# Voltmeter_PCB_RTC_f.net
KiCad netlist of a schematic drawn in EAGLE
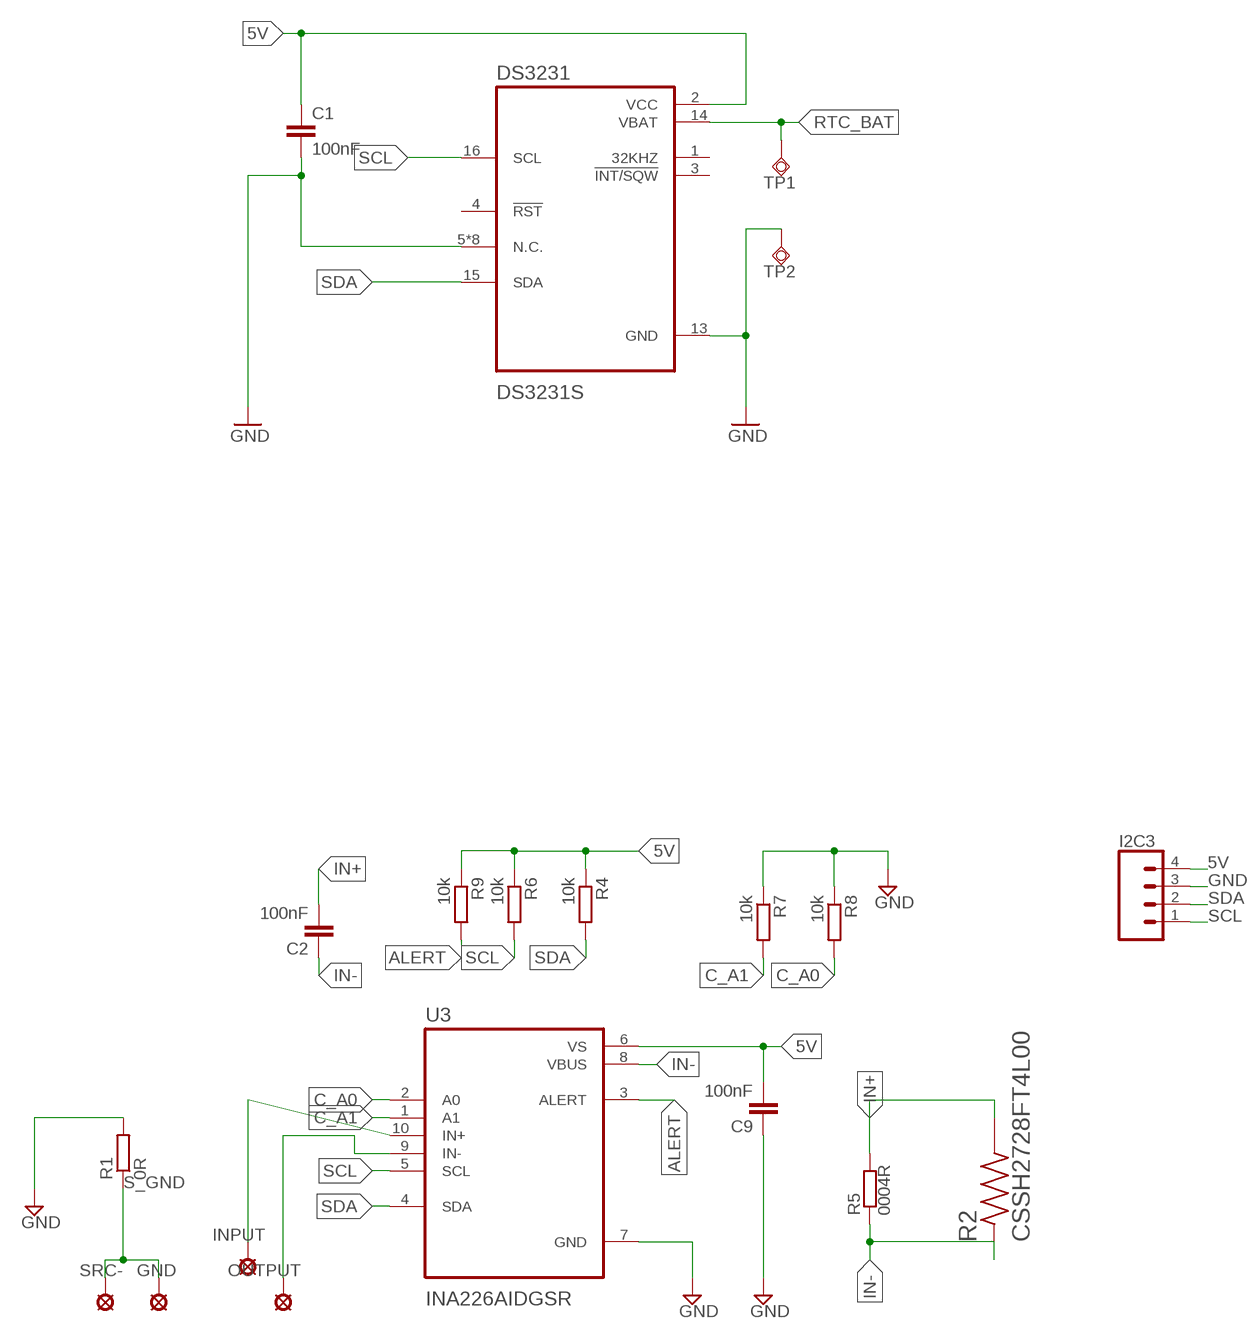
[diagram p0: schematic, sheet 1]

(export (version "E")
  (design (tool "Eeschema 10.0.6"))
  (components
    (comp (ref "C1")
      (value "100nF")
      (footprint "eagle-import:C0603")
      (libsource (lib "eagle-import") (part "resistor_348_C-EUC0603"))
    )
    (comp (ref "C2")
      (value "100nF")
      (footprint "eagle-import:C0603")
      (libsource (lib "eagle-import") (part "C-EUC0603"))
    )
    (comp (ref "C9")
      (value "100nF")
      (footprint "eagle-import:C0603")
      (libsource (lib "eagle-import") (part "C-EUC0603"))
    )
    (comp (ref "DS3231")
      (value "DS3231S")
      (footprint "eagle-import:SOIC127P1032X265-16N")
      (fields (field (name "MF") "Maxim Integrated"))
      (libsource (lib "eagle-import") (part "DS3231S"))
    )
    (comp (ref "GND")
      (value "SE14")
      (footprint "eagle-import:SE14")
      (libsource (lib "eagle-import") (part "SE14"))
    )
    (comp (ref "I2C3")
      (value "CONN_041X04_NO_SILK")
      (footprint "eagle-import:1X04_NO_SILK")
      (libsource (lib "eagle-import") (part "CONN_041X04_NO_SILK"))
    )
    (comp (ref "INPUT")
      (value "SE14")
      (footprint "eagle-import:SE14")
      (libsource (lib "eagle-import") (part "SE14"))
    )
    (comp (ref "OUTPUT")
      (value "SE14")
      (footprint "eagle-import:SE14")
      (libsource (lib "eagle-import") (part "SE14"))
    )
    (comp (ref "R1")
      (value "0R")
      (footprint "eagle-import:R1206")
      (libsource (lib "eagle-import") (part "R-EU_R1206"))
    )
    (comp (ref "R2")
      (value "CSSH2728FT4L00")
      (footprint "eagle-import:RESC6771X124N")
      (fields (field (name "MF") "Stackpole Electronics Inc"))
      (libsource (lib "eagle-import") (part "CSSH2728FT4L00"))
    )
    (comp (ref "R4")
      (value "10k")
      (footprint "eagle-import:R0603")
      (libsource (lib "eagle-import") (part "R-EU_R0603"))
    )
    (comp (ref "R5")
      (value "0004R")
      (footprint "eagle-import:BVS")
      (libsource (lib "eagle-import") (part "BVS"))
    )
    (comp (ref "R6")
      (value "10k")
      (footprint "eagle-import:R0603")
      (libsource (lib "eagle-import") (part "R-EU_R0603"))
    )
    (comp (ref "R7")
      (value "10k")
      (footprint "eagle-import:R0603")
      (libsource (lib "eagle-import") (part "R-EU_R0603"))
    )
    (comp (ref "R8")
      (value "10k")
      (footprint "eagle-import:R0603")
      (libsource (lib "eagle-import") (part "R-EU_R0603"))
    )
    (comp (ref "R9")
      (value "10k")
      (footprint "eagle-import:R0603")
      (libsource (lib "eagle-import") (part "R-EU_R0603"))
    )
    (comp (ref "SRC-")
      (value "SE14")
      (footprint "eagle-import:SE14")
      (libsource (lib "eagle-import") (part "SE14"))
    )
    (comp (ref "TP1")
      (value "TPSQB1,27")
      (footprint "eagle-import:B1,27")
      (libsource (lib "eagle-import") (part "TPSQB1,27"))
    )
    (comp (ref "TP2")
      (value "TPSQB1,27")
      (footprint "eagle-import:B1,27")
      (libsource (lib "eagle-import") (part "TPSQB1,27"))
    )
    (comp (ref "U3")
      (value "INA226AIDGSR")
      (footprint "eagle-import:SOP50P490X110-10N")
      (fields (field (name "MF") "Texas Instruments"))
      (libsource (lib "eagle-import") (part "INA226AIDGSR"))
    )
  )
  (nets
    (net (code "1") (name "/S_GND") (class "Default")
      (node (ref "GND") (pin "MP") (pinfunction "MP_MP") (pintype "passive"))
      (node (ref "R1") (pin "1") (pinfunction "1_1") (pintype "passive"))
      (node (ref "SRC-") (pin "MP") (pinfunction "MP_MP") (pintype "passive"))
    )
    (net (code "2") (name "5V") (class "Default")
      (node (ref "C1") (pin "1") (pinfunction "1_1") (pintype "passive"))
      (node (ref "C9") (pin "2") (pinfunction "2_2") (pintype "passive"))
      (node (ref "DS3231") (pin "2") (pinfunction "VCC_2") (pintype "power_in"))
      (node (ref "I2C3") (pin "4") (pinfunction "4_4") (pintype "passive"))
      (node (ref "R4") (pin "1") (pinfunction "1_1") (pintype "passive"))
      (node (ref "R6") (pin "1") (pinfunction "1_1") (pintype "passive"))
      (node (ref "R9") (pin "1") (pinfunction "1_1") (pintype "passive"))
      (node (ref "U3") (pin "6") (pinfunction "VS_6") (pintype "power_in"))
    )
    (net (code "3") (name "ALERT") (class "Default")
      (node (ref "R9") (pin "2") (pinfunction "2_2") (pintype "passive"))
      (node (ref "U3") (pin "3") (pinfunction "ALERT_3") (pintype "output"))
    )
    (net (code "4") (name "C_A0") (class "Default")
      (node (ref "R8") (pin "2") (pinfunction "2_2") (pintype "passive"))
      (node (ref "U3") (pin "2") (pinfunction "A0_2") (pintype "input"))
    )
    (net (code "5") (name "C_A1") (class "Default")
      (node (ref "R7") (pin "2") (pinfunction "2_2") (pintype "passive"))
      (node (ref "U3") (pin "1") (pinfunction "A1_1") (pintype "input"))
    )
    (net (code "6") (name "GND") (class "Default")
      (node (ref "C1") (pin "2") (pinfunction "2_2") (pintype "passive"))
      (node (ref "C9") (pin "1") (pinfunction "1_1") (pintype "passive"))
      (node (ref "DS3231") (pin "10") (pinfunction "N.C._10") (pintype "bidirectional"))
      (node (ref "DS3231") (pin "11") (pinfunction "N.C._11") (pintype "bidirectional"))
      (node (ref "DS3231") (pin "12") (pinfunction "N.C._12") (pintype "bidirectional"))
      (node (ref "DS3231") (pin "13") (pinfunction "GND_13") (pintype "power_in"))
      (node (ref "DS3231") (pin "5") (pinfunction "N.C._5") (pintype "bidirectional"))
      (node (ref "DS3231") (pin "6") (pinfunction "N.C._6") (pintype "bidirectional"))
      (node (ref "DS3231") (pin "7") (pinfunction "N.C._7") (pintype "bidirectional"))
      (node (ref "DS3231") (pin "8") (pinfunction "N.C._8") (pintype "bidirectional"))
      (node (ref "DS3231") (pin "9") (pinfunction "N.C._9") (pintype "bidirectional"))
      (node (ref "I2C3") (pin "3") (pinfunction "3_3") (pintype "passive"))
      (node (ref "R1") (pin "2") (pinfunction "2_2") (pintype "passive"))
      (node (ref "R7") (pin "1") (pinfunction "1_1") (pintype "passive"))
      (node (ref "R8") (pin "1") (pinfunction "1_1") (pintype "passive"))
      (node (ref "TP2") (pin "TP") (pinfunction "TP_TP") (pintype "input"))
      (node (ref "U3") (pin "7") (pinfunction "GND_7") (pintype "power_in"))
    )
    (net (code "7") (name "IN+") (class "Default")
      (node (ref "C2") (pin "2") (pinfunction "2_2") (pintype "passive"))
      (node (ref "OUTPUT") (pin "MP") (pinfunction "MP_MP") (pintype "passive"))
      (node (ref "R2") (pin "2") (pinfunction "2_2") (pintype "passive"))
      (node (ref "R5") (pin "1") (pinfunction "1_1") (pintype "passive"))
      (node (ref "U3") (pin "9") (pinfunction "IN-_9") (pintype "input"))
    )
    (net (code "8") (name "IN-") (class "Default")
      (node (ref "C2") (pin "1") (pinfunction "1_1") (pintype "passive"))
      (node (ref "INPUT") (pin "MP") (pinfunction "MP_MP") (pintype "passive"))
      (node (ref "R2") (pin "1") (pinfunction "1_1") (pintype "passive"))
      (node (ref "R5") (pin "2") (pinfunction "2_2") (pintype "passive"))
      (node (ref "U3") (pin "10") (pinfunction "IN+_10") (pintype "input"))
      (node (ref "U3") (pin "8") (pinfunction "VBUS_8") (pintype "power_in"))
    )
    (net (code "9") (name "RTC_BAT") (class "Default")
      (node (ref "DS3231") (pin "14") (pinfunction "VBAT_14") (pintype "power_in"))
      (node (ref "TP1") (pin "TP") (pinfunction "TP_TP") (pintype "input"))
    )
    (net (code "10") (name "SCL") (class "Default")
      (node (ref "DS3231") (pin "16") (pinfunction "SCL_16") (pintype "input"))
      (node (ref "I2C3") (pin "1") (pinfunction "1_1") (pintype "passive"))
      (node (ref "R6") (pin "2") (pinfunction "2_2") (pintype "passive"))
      (node (ref "U3") (pin "5") (pinfunction "SCL_5") (pintype "input"))
    )
    (net (code "11") (name "SDA") (class "Default")
      (node (ref "DS3231") (pin "15") (pinfunction "SDA_15") (pintype "bidirectional"))
      (node (ref "I2C3") (pin "2") (pinfunction "2_2") (pintype "passive"))
      (node (ref "R4") (pin "2") (pinfunction "2_2") (pintype "passive"))
      (node (ref "U3") (pin "4") (pinfunction "SDA_4") (pintype "bidirectional"))
    )
    (net (code "12") (name "unconnected-(DS3231-32KHZ-Pad1)") (class "Default")
      (node (ref "DS3231") (pin "1") (pinfunction "32KHZ_1") (pintype "output"))
    )
    (net (code "13") (name "unconnected-(DS3231-~{INT{slash}SQW}-Pad3)") (class "Default")
      (node (ref "DS3231") (pin "3") (pinfunction "~{INT/SQW}_3") (pintype "output"))
    )
    (net (code "14") (name "unconnected-(DS3231-~{RST}-Pad4)") (class "Default")
      (node (ref "DS3231") (pin "4") (pinfunction "~{RST}_4") (pintype "bidirectional"))
    )
  )
)
